# VRef_2.net
KiCad netlist of a schematic drawn in Altium Designer
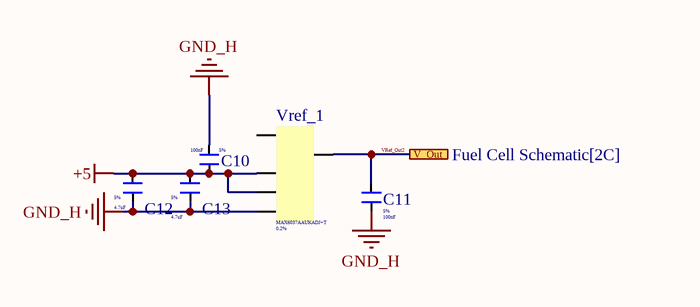
[diagram p0: VRef_2.SchDoc]

(export (version "E")
  (design (tool "Eeschema 10.0.6"))
  (components
    (comp (ref "C10")
      (value "~")
      (footprint "Capacitor_Kemet_0805")
      (description "Cap Ceramic 0.1uF 16V X7R 5% SMD 0805 125°C Plastic T/R")
      (fields
        (field (name "MANUFACTURER") "KEMET")
        (field (name "MANUFACTURER PART NUMBER") "C0805C104J4RACTU")
        (field (name "DISSIPATION FACTOR") "5%")
        (field (name "CAPACITANCE") "100nF")
      )
      (libsource (lib "Schlib1") (part "C0805C104J4RACTU"))
    )
    (comp (ref "C11")
      (value "~")
      (footprint "Capacitor_Kemet_0805")
      (description "Cap Ceramic 0.1uF 16V X7R 5% SMD 0805 125°C Plastic T/R")
      (fields
        (field (name "MANUFACTURER") "KEMET")
        (field (name "MANUFACTURER PART NUMBER") "C0805C104J4RACTU")
        (field (name "DISSIPATION FACTOR") "5%")
        (field (name "CAPACITANCE") "100nF")
      )
      (libsource (lib "Schlib1") (part "C0805C104J4RACTU"))
    )
    (comp (ref "C12")
      (value "~")
      (footprint "Capacitor_Kemet_0805")
      (description "CAP CER 4.7UF 16V X7R 0805")
      (fields
        (field (name "MANUFACTURER") "KEMET")
        (field (name "MANUFACTURER PART NUMBER") "C0805C475J4RACAUTO")
        (field (name "TOLERANCE") "5%")
        (field (name "CAPACITANCE") "4.7uF")
      )
      (libsource (lib "Schlib1") (part "C0805C475J4RACAUTO"))
    )
    (comp (ref "C13")
      (value "~")
      (footprint "Capacitor_Kemet_0805")
      (description "CAP CER 4.7UF 16V X7R 0805")
      (fields
        (field (name "MANUFACTURER") "KEMET")
        (field (name "MANUFACTURER PART NUMBER") "C0805C475J4RACAUTO")
        (field (name "TOLERANCE") "5%")
        (field (name "CAPACITANCE") "4.7uF")
      )
      (libsource (lib "Schlib1") (part "C0805C475J4RACAUTO"))
    )
    (comp (ref "Vref_1")
      (value "~")
      (footprint "VRef")
      (description "IC VREF SERIES ADJ 0.2% SOT23-5")
      (fields
        (field (name "MANUFACTURER") "Maxim")
        (field (name "MANUFACTURER PART NUMBER") "MAX6037AAUKADJ+T")
        (field (name "TOLERANCE") "0.2%")
      )
      (libsource (lib "Schlib1") (part "MAX6037AAUKADJ+T"))
    )
  )
  (nets
    (net (code "1") (name "+5") (class "Default")
      (node (ref "C10") (pin "1") (pinfunction "1_1") (pintype "passive"))
      (node (ref "C12") (pin "2") (pinfunction "2_2") (pintype "passive"))
      (node (ref "C13") (pin "2") (pinfunction "2_2") (pintype "passive"))
      (node (ref "Vref_1") (pin "3") (pinfunction "SHDN_3") (pintype "passive"))
      (node (ref "Vref_1") (pin "4") (pinfunction "In_4") (pintype "passive"))
    )
    (net (code "2") (name "/VRef_Out2") (class "Default")
      (node (ref "C11") (pin "2") (pinfunction "2_2") (pintype "passive"))
      (node (ref "Vref_1") (pin "5") (pinfunction "OUT_5") (pintype "passive"))
    )
    (net (code "3") (name "GND_H") (class "Default")
      (node (ref "C10") (pin "2") (pinfunction "2_2") (pintype "passive"))
      (node (ref "C11") (pin "1") (pinfunction "1_1") (pintype "passive"))
      (node (ref "C12") (pin "1") (pinfunction "1_1") (pintype "passive"))
      (node (ref "C13") (pin "1") (pinfunction "1_1") (pintype "passive"))
      (node (ref "Vref_1") (pin "2") (pinfunction "GND_2") (pintype "passive"))
    )
    (net (code "4") (name "unconnected-(Vref_1-ADJ-Pad1)") (class "Default")
      (node (ref "Vref_1") (pin "1") (pinfunction "ADJ_1") (pintype "passive"))
    )
  )
)
